# H05R1_Frontend_2.net
KiCad netlist of a schematic drawn in Altium Designer
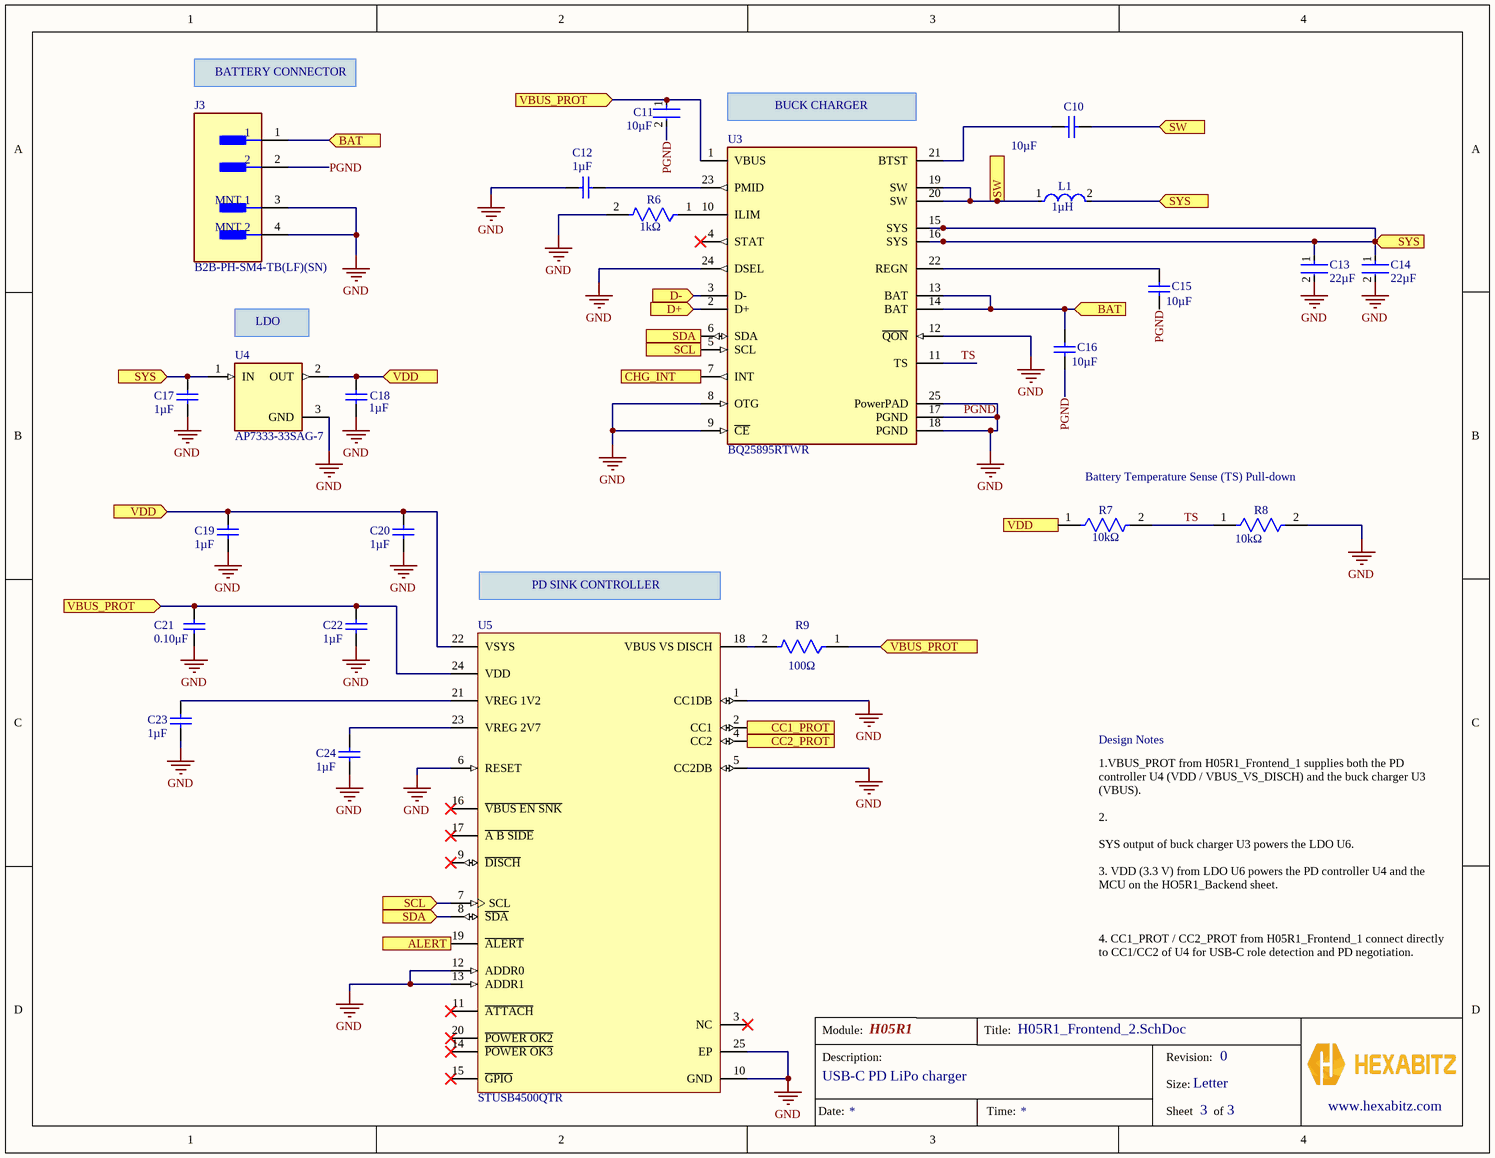
[diagram p0: H05R1_Frontend_2.SchDoc]

(export (version "E")
  (design (tool "Eeschema 10.0.6"))
  (components
    (comp (ref "C10")
      (value "10µF")
      (footprint "CAPC1608X90X35ML10T15")
      (fields
        (field (name "PART NUMBER") "GRM188R71C473KA01D")
        (field (name "MANUFACTURER") "Murata")
        (field (name "OCTOPART") "https://octopart.com/part/murata/GRM21BZ71E106KE15L")
      )
      (libsource (lib "Altium Content Vault") (part "CAP"))
    )
    (comp (ref "C11")
      (value "10µF")
      (footprint "FP-GRM21B-0_2-e0_2_0_7-IPC_B")
      (description "Chip Multilayer Ceramic Capacitors for General Purpose, 0805, 10uF, X7R, 15%, 10%, 25V")
      (fields (field (name "MPN") "GRM21BZ71E106KE15L"))
      (libsource (lib "Altium Content Vault") (part "b4654b650e69147ec39a6b967a45e02"))
    )
    (comp (ref "C12")
      (value "1µF")
      (footprint "CAPC1608X90X35ML10T15")
      (fields
        (field (name "MANUFACTURER") "Murata")
        (field (name "PART NUMBER") "GRM188R71C105KA12D")
        (field (name "OCTOPART") "https://octopart.com/search?q=GRM188R71C105KA12D&currency=USD&specs=0")
      )
      (libsource (lib "Altium Content Vault") (part "CAP"))
    )
    (comp (ref "C13")
      (value "22µF")
      (footprint "FP-GRM21B-0_15-MFG")
      (description "Chip Multilayer Ceramic Capacitors for General Purpose, 0805, 22uF, X5R, 15%, 20%, 6.3V")
      (fields (field (name "VOLTAGE") "6.3V") (field (name "TOLERANCE") "20%"))
      (libsource (lib "Altium Content Vault") (part "b4654b650e69147ec39a6b967a45e02"))
    )
    (comp (ref "C14")
      (value "22µF")
      (footprint "FP-GRM21B-0_15-MFG")
      (description "Chip Multilayer Ceramic Capacitors for General Purpose, 0805, 22uF, X5R, 15%, 20%, 6.3V")
      (fields (field (name "VOLTAGE") "6.3V") (field (name "TOLERANCE") "20%"))
      (libsource (lib "Altium Content Vault") (part "b4654b650e69147ec39a6b967a45e02"))
    )
    (comp (ref "C15")
      (value "10µF")
      (footprint "CAPC1608X90X35ML10T15")
      (fields
        (field (name "MANUFACTURER") "Murata")
        (field (name "PART NUMBER") "GRM188R71C105KA12D")
        (field (name "OCTOPART") "https://octopart.com/part/murata/GRM21BZ71E106KE15L")
      )
      (libsource (lib "Altium Content Vault") (part "CAP"))
    )
    (comp (ref "C16")
      (value "10µF")
      (footprint "CAPC2013X135X45ML10T25")
      (description "Multilayer Ceramic Capacitors MLCC Surface Mount 0805 10uF 6.3 Volts X5R")
      (fields (field (name "PART NUMBER") "GRM21BR60J106KE19L") (field (name "MANUFACTURER") "Murata"))
      (libsource (lib "Altium Content Vault") (part "CAP"))
    )
    (comp (ref "C17")
      (value "1µF")
      (footprint "CAPC1608X90X35ML10T15")
      (description "Ceramic Capacitor, Ceramic, 16V, 10% +Tol, 10% -Tol, X7R, 15% TC, 1uF, Surface Mount, 0603")
      (fields (field (name "MANUFACTURER") "Murata") (field (name "PART NUMBER") "GRM188R71C105KA12D"))
      (libsource (lib "Altium Content Vault") (part "CAP"))
    )
    (comp (ref "C18")
      (value "1µF")
      (footprint "CAPC1608X90X35ML10T15")
      (description "Ceramic Capacitor, Ceramic, 16V, 10% +Tol, 10% -Tol, X7R, 15% TC, 1uF, Surface Mount, 0603")
      (fields (field (name "MANUFACTURER") "Murata") (field (name "PART NUMBER") "GRM188R71C105KA12D"))
      (libsource (lib "Altium Content Vault") (part "CAP"))
    )
    (comp (ref "C19")
      (value "1µF")
      (footprint "MURA-0603_H_0.9_M")
      (description "CAP, Ceramic, 0.1 uF, 10%, 16 V, 0603, RoHS, Tape and Reel")
      (fields (field (name "MANUFACTURER") "Murata") (field (name "TOLERANCE") "10%"))
      (libsource (lib "Altium Content Vault") (part "CAP-NP-2"))
    )
    (comp (ref "C20")
      (value "1µF")
      (footprint "CAPC1608X90X35ML10T15")
      (description "Ceramic Capacitor, Ceramic, 16V, 10% +Tol, 10% -Tol, X7R, 15% TC, 1uF, Surface Mount, 0603")
      (fields (field (name "MANUFACTURER") "Murata") (field (name "PART NUMBER") "GRM188R71C105KA12D"))
      (libsource (lib "Altium Content Vault") (part "CAP"))
    )
    (comp (ref "C21")
      (value "0.10μF")
      (footprint "CAPC1608X90X35LL10T15")
      (description "25V 100Nf X7R 10% 0603 Multilayer Ceramic Capacitors Mlcc Smd/Smt Rohs")
      (fields (field (name "PART NUMBER") "GRM188R71E104KA01D") (field (name "MANUFACTURER") "Murata"))
      (libsource (lib "Altium Content Vault") (part "CAP"))
    )
    (comp (ref "C22")
      (value "1µF")
      (footprint "CAPC1608X90X35ML10T15")
      (fields
        (field (name "MANUFACTURER") "Murata")
        (field (name "PART NUMBER") "GRM188R71E105KA12D")
        (field (name "OCTOPART") "https://octopart.com/part/murata/GRM188R71E105KA12D")
      )
      (libsource (lib "Altium Content Vault") (part "CAP"))
    )
    (comp (ref "C23")
      (value "1µF")
      (footprint "CAPC1608X90X35ML10T15")
      (description "Ceramic Capacitor, Ceramic, 25V, 10% +Tol, 10% -Tol, X7R, 15% TC, 1uF, Surface Mount, 0603")
      (fields (field (name "MANUFACTURER") "Murata") (field (name "PART NUMBER") "GRM188R71E105KA12D"))
      (libsource (lib "Altium Content Vault") (part "CAP"))
    )
    (comp (ref "C24")
      (value "1µF")
      (footprint "CAPC1608X90X35ML10T15")
      (description "Ceramic Capacitor, Ceramic, 25V, 10% +Tol, 10% -Tol, X7R, 15% TC, 1uF, Surface Mount, 0603")
      (fields (field (name "MANUFACTURER") "Murata") (field (name "PART NUMBER") "GRM188R71E105KA12D"))
      (libsource (lib "Altium Content Vault") (part "CAP"))
    )
    (comp (ref "J3")
      (value "B2B-PH-SM4-TB(LF)(SN)")
      (footprint "FP-B2B-PH-SM4-TB_LF_SN-MFG")
      (description "CONN HEADER SMD 2POS 2MM")
      (fields (field (name "OCTOPART") "https://octopart.com/part/jst/B2B-PH-SM4-TB%28LF%29%28SN%29"))
      (libsource (lib "Altium Content Vault") (part "56ec3178a87b3978bdc1b3682cd516a"))
    )
    (comp (ref "L1")
      (value "1µH")
      (footprint "FP-XAL4020-102MEC-MFG")
      (description "Fixed Inductors 1uH 20% 9.6A 14.60mOhms AEC-Q200")
      (fields
        (field (name "MANUFACTURER") "Coilcraft")
        (field (name "OCTOPART") "https://octopart.com/xal4020-102mec-coilcraft-13142161")
      )
      (libsource (lib "Altium Content Vault") (part "725321dda6339637d4d059423bc1c3c"))
    )
    (comp (ref "R6")
      (value "1kΩ")
      (footprint "FP-RC0603-0_55-IPC_C")
      (description "RES 1K OHM 1% 1/10W 0603")
      (fields (field (name "TOLERANCE") "1%") (field (name "MPN") "RC0603FR-071KL"))
      (libsource (lib "Altium Content Vault") (part "1029c3af85768c4190bb7ad29bc67b5"))
    )
    (comp (ref "R7")
      (value "10kΩ")
      (footprint "FP-RC0603-0_55-IPC_C")
      (description "RES 10K OHM 1% 1/10W 0603")
      (fields
        (field (name "TOLERANCE") "1%")
        (field (name "OCTOPART") "https://octopart.com/search?q=RC0603FR-0710KL&currency=USD&specs=0")
      )
      (libsource (lib "Altium Content Vault") (part "1029c3af85768c4190bb7ad29bc67b5"))
    )
    (comp (ref "R8")
      (value "10kΩ")
      (footprint "FP-RC0603-0_55-IPC_C")
      (description "RES 10K OHM 1% 1/10W 0603")
      (fields
        (field (name "TOLERANCE") "1%")
        (field (name "OCTOPART") "https://octopart.com/search?q=RC0603FR-0710KL&currency=USD&specs=0")
      )
      (libsource (lib "Altium Content Vault") (part "1029c3af85768c4190bb7ad29bc67b5"))
    )
    (comp (ref "R9")
      (value "100Ω")
      (footprint "FP-RC0603-0_55-MFG")
      (fields (field (name "TOLERANCE") "1%") (field (name "MPN") "RC0603FR-07100RL"))
      (libsource (lib "Altium Content Vault") (part "1029c3af85768c4190bb7ad29bc67b5"))
    )
    (comp (ref "U3")
      (value "BQ25895RTWR")
      (footprint "FP-RTW0024H-IPC_B")
      (description "IC NVDC CHARGER I2C 24WQFN")
      (fields (field (name "OCTOPART") "https://octopart.com/bq25895rtwr-texas+instruments-56801238"))
      (libsource (lib "Altium Content Vault") (part "9676aa47796aa55c38f1d5ce4e9995c"))
    )
    (comp (ref "U4")
      (value "AP7333-33SAG-7")
      (footprint "FP-SOT23-MFG")
      (description "IC REG LINEAR 3.3V 300MA SOT23-3")
      (fields
        (field (name "MANUFACTURER") "Diodes Inc.")
        (field (name "OCTOPART") "https://octopart.com/ap7333-33sag-7-diodes+inc.-17947531")
      )
      (libsource (lib "Altium Content Vault") (part "99e442a359f93c082ad1a9b51a2d33f"))
    )
    (comp (ref "U5")
      (value "STUSB4500QTR")
      (footprint "FP-QFN-24-EP_4x4-MFG")
      (description "4.1V~22V USB 2.0 I2C Controllers Interface ICs STUSB45 Controller 24-VFQFN Exposed Pad")
      (fields (field (name "OCTOPART") "https://octopart.com/stusb4500qtr-stmicroelectronics-91765108"))
      (libsource (lib "Altium Content Vault") (part "STUSB4500QTR"))
    )
  )
  (nets
    (net (code "1") (name "/ALERT") (class "Default")
      (node (ref "U5") (pin "19") (pinfunction "~{ALERT}_19") (pintype "open_collector"))
    )
    (net (code "2") (name "/BAT") (class "Default")
      (node (ref "C16") (pin "2") (pinfunction "2_2") (pintype "passive"))
      (node (ref "J3") (pin "1") (pinfunction "1_1") (pintype "passive"))
      (node (ref "U3") (pin "13") (pinfunction "BAT_13") (pintype "power_in"))
      (node (ref "U3") (pin "14") (pinfunction "BAT_14") (pintype "power_in"))
    )
    (net (code "3") (name "/CC1_PROT") (class "Default")
      (node (ref "U5") (pin "2") (pinfunction "CC1_2") (pintype "bidirectional"))
    )
    (net (code "4") (name "/CC2_PROT") (class "Default")
      (node (ref "U5") (pin "4") (pinfunction "CC2_4") (pintype "bidirectional"))
    )
    (net (code "5") (name "/CHG_INT") (class "Default")
      (node (ref "U3") (pin "7") (pinfunction "INT_7") (pintype "output"))
    )
    (net (code "6") (name "/D+") (class "Default")
      (node (ref "U3") (pin "2") (pinfunction "D+_2") (pintype "passive"))
    )
    (net (code "7") (name "/D-") (class "Default")
      (node (ref "U3") (pin "3") (pinfunction "D-_3") (pintype "passive"))
    )
    (net (code "8") (name "/SCL") (class "Default")
      (node (ref "U3") (pin "5") (pinfunction "SCL_5") (pintype "input"))
      (node (ref "U5") (pin "7") (pinfunction "SCL_7") (pintype "input"))
    )
    (net (code "9") (name "/SDA") (class "Default")
      (node (ref "U3") (pin "6") (pinfunction "SDA_6") (pintype "bidirectional"))
      (node (ref "U5") (pin "8") (pinfunction "~{SDA}_8") (pintype "bidirectional"))
    )
    (net (code "10") (name "/SW") (class "Default")
      (node (ref "C10") (pin "1") (pinfunction "1_1") (pintype "passive"))
      (node (ref "L1") (pin "1") (pinfunction "1_1") (pintype "passive"))
      (node (ref "U3") (pin "19") (pinfunction "SW_19") (pintype "passive"))
      (node (ref "U3") (pin "20") (pinfunction "SW_20") (pintype "passive"))
    )
    (net (code "11") (name "/SYS") (class "Default")
      (node (ref "C13") (pin "1") (pinfunction "1_1") (pintype "passive"))
      (node (ref "C14") (pin "1") (pinfunction "1_1") (pintype "passive"))
      (node (ref "C17") (pin "2") (pinfunction "2_2") (pintype "passive"))
      (node (ref "L1") (pin "2") (pinfunction "2_2") (pintype "passive"))
      (node (ref "U3") (pin "15") (pinfunction "SYS_15") (pintype "power_in"))
      (node (ref "U3") (pin "16") (pinfunction "SYS_16") (pintype "power_in"))
      (node (ref "U4") (pin "1") (pinfunction "IN_1") (pintype "input"))
    )
    (net (code "12") (name "/TS") (class "Default")
      (node (ref "R7") (pin "2") (pinfunction "2_2") (pintype "passive"))
      (node (ref "R8") (pin "1") (pinfunction "1_1") (pintype "passive"))
      (node (ref "U3") (pin "11") (pinfunction "TS_11") (pintype "passive"))
    )
    (net (code "13") (name "/VBUS_PROT") (class "Default")
      (node (ref "C11") (pin "1") (pinfunction "1_1") (pintype "passive"))
      (node (ref "C21") (pin "2") (pinfunction "2_2") (pintype "passive"))
      (node (ref "C22") (pin "2") (pinfunction "2_2") (pintype "passive"))
      (node (ref "R9") (pin "1") (pinfunction "1_1") (pintype "passive"))
      (node (ref "U3") (pin "1") (pinfunction "VBUS_1") (pintype "power_in"))
      (node (ref "U5") (pin "24") (pinfunction "VDD_24") (pintype "power_in"))
    )
    (net (code "14") (name "/VDD") (class "Default")
      (node (ref "C18") (pin "2") (pinfunction "2_2") (pintype "passive"))
      (node (ref "C19") (pin "2") (pinfunction "2_2") (pintype "passive"))
      (node (ref "C20") (pin "2") (pinfunction "2_2") (pintype "passive"))
      (node (ref "R7") (pin "1") (pinfunction "1_1") (pintype "passive"))
      (node (ref "U4") (pin "2") (pinfunction "OUT_2") (pintype "output"))
      (node (ref "U5") (pin "22") (pinfunction "VSYS_22") (pintype "power_in"))
    )
    (net (code "15") (name "GND") (class "Default")
      (node (ref "C11") (pin "2") (pinfunction "2_2") (pintype "passive"))
      (node (ref "C12") (pin "1") (pinfunction "1_1") (pintype "passive"))
      (node (ref "C13") (pin "2") (pinfunction "2_2") (pintype "passive"))
      (node (ref "C14") (pin "2") (pinfunction "2_2") (pintype "passive"))
      (node (ref "C15") (pin "1") (pinfunction "1_1") (pintype "passive"))
      (node (ref "C16") (pin "1") (pinfunction "1_1") (pintype "passive"))
      (node (ref "C17") (pin "1") (pinfunction "1_1") (pintype "passive"))
      (node (ref "C18") (pin "1") (pinfunction "1_1") (pintype "passive"))
      (node (ref "C19") (pin "1") (pinfunction "1_1") (pintype "passive"))
      (node (ref "C20") (pin "1") (pinfunction "1_1") (pintype "passive"))
      (node (ref "C21") (pin "1") (pinfunction "1_1") (pintype "passive"))
      (node (ref "C22") (pin "1") (pinfunction "1_1") (pintype "passive"))
      (node (ref "C23") (pin "1") (pinfunction "1_1") (pintype "passive"))
      (node (ref "C24") (pin "1") (pinfunction "1_1") (pintype "passive"))
      (node (ref "J3") (pin "2") (pinfunction "2_2") (pintype "passive"))
      (node (ref "J3") (pin "3") (pinfunction "MNT_1_3") (pintype "passive"))
      (node (ref "J3") (pin "4") (pinfunction "MNT_2_4") (pintype "passive"))
      (node (ref "R6") (pin "2") (pinfunction "2_2") (pintype "passive"))
      (node (ref "R8") (pin "2") (pinfunction "2_2") (pintype "passive"))
      (node (ref "U3") (pin "12") (pinfunction "~{QON}_12") (pintype "input"))
      (node (ref "U3") (pin "17") (pinfunction "PGND_17") (pintype "power_in"))
      (node (ref "U3") (pin "18") (pinfunction "PGND_18") (pintype "power_in"))
      (node (ref "U3") (pin "24") (pinfunction "DSEL_24") (pintype "output"))
      (node (ref "U3") (pin "25") (pinfunction "PowerPAD_25") (pintype "power_in"))
      (node (ref "U3") (pin "8") (pinfunction "OTG_8") (pintype "input"))
      (node (ref "U3") (pin "9") (pinfunction "~{CE}_9") (pintype "input"))
      (node (ref "U4") (pin "3") (pinfunction "GND_3") (pintype "power_in"))
      (node (ref "U5") (pin "1") (pinfunction "CC1DB_1") (pintype "bidirectional"))
      (node (ref "U5") (pin "10") (pinfunction "GND_10") (pintype "power_in"))
      (node (ref "U5") (pin "12") (pinfunction "ADDR0_12") (pintype "input"))
      (node (ref "U5") (pin "13") (pinfunction "ADDR1_13") (pintype "input"))
      (node (ref "U5") (pin "25") (pinfunction "EP_25") (pintype "power_in"))
      (node (ref "U5") (pin "5") (pinfunction "CC2DB_5") (pintype "bidirectional"))
      (node (ref "U5") (pin "6") (pinfunction "RESET_6") (pintype "input"))
    )
    (net (code "16") (name "Net-(U3-BTST)") (class "Default")
      (node (ref "C10") (pin "2") (pinfunction "2_2") (pintype "passive"))
      (node (ref "U3") (pin "21") (pinfunction "BTST_21") (pintype "power_in"))
    )
    (net (code "17") (name "Net-(U3-ILIM)") (class "Default")
      (node (ref "R6") (pin "1") (pinfunction "1_1") (pintype "passive"))
      (node (ref "U3") (pin "10") (pinfunction "ILIM_10") (pintype "passive"))
    )
    (net (code "18") (name "Net-(U3-PMID)") (class "Default")
      (node (ref "C12") (pin "2") (pinfunction "2_2") (pintype "passive"))
      (node (ref "U3") (pin "23") (pinfunction "PMID_23") (pintype "output"))
    )
    (net (code "19") (name "Net-(U3-REGN)") (class "Default")
      (node (ref "C15") (pin "2") (pinfunction "2_2") (pintype "passive"))
      (node (ref "U3") (pin "22") (pinfunction "REGN_22") (pintype "power_in"))
    )
    (net (code "20") (name "Net-(U5-VBUS_VS_DISCH)") (class "Default")
      (node (ref "R9") (pin "2") (pinfunction "2_2") (pintype "passive"))
      (node (ref "U5") (pin "18") (pinfunction "VBUS_VS_DISCH_18") (pintype "power_in"))
    )
    (net (code "21") (name "Net-(U5-VREG_1V2)") (class "Default")
      (node (ref "C23") (pin "2") (pinfunction "2_2") (pintype "passive"))
      (node (ref "U5") (pin "21") (pinfunction "VREG_1V2_21") (pintype "power_in"))
    )
    (net (code "22") (name "Net-(U5-VREG_2V7)") (class "Default")
      (node (ref "C24") (pin "2") (pinfunction "2_2") (pintype "passive"))
      (node (ref "U5") (pin "23") (pinfunction "VREG_2V7_23") (pintype "power_in"))
    )
    (net (code "23") (name "unconnected-(U3-STAT-Pad4)") (class "Default")
      (node (ref "U3") (pin "4") (pinfunction "STAT_4") (pintype "output+no_connect"))
    )
    (net (code "24") (name "unconnected-(U5-NC-Pad3)") (class "Default")
      (node (ref "U5") (pin "3") (pinfunction "NC_3") (pintype "passive+no_connect"))
    )
    (net (code "25") (name "unconnected-(U5-~{ATTACH}-Pad11)") (class "Default")
      (node (ref "U5") (pin "11") (pinfunction "~{ATTACH}_11") (pintype "open_collector+no_connect"))
    )
    (net (code "26") (name "unconnected-(U5-~{A_B_SIDE}-Pad17)") (class "Default")
      (node (ref "U5") (pin "17") (pinfunction "~{A_B_SIDE}_17") (pintype "open_collector+no_connect"))
    )
    (net (code "27") (name "unconnected-(U5-~{DISCH}-Pad9)") (class "Default")
      (node (ref "U5") (pin "9") (pinfunction "~{DISCH}_9") (pintype "bidirectional+no_connect"))
    )
    (net (code "28") (name "unconnected-(U5-~{GPIO}-Pad15)") (class "Default")
      (node (ref "U5") (pin "15") (pinfunction "~{GPIO}_15") (pintype "open_collector+no_connect"))
    )
    (net (code "29") (name "unconnected-(U5-~{POWER_OK2}-Pad20)") (class "Default")
      (node (ref "U5") (pin "20") (pinfunction "~{POWER_OK2}_20") (pintype "power_in+no_connect"))
    )
    (net (code "30") (name "unconnected-(U5-~{POWER_OK3}-Pad14)") (class "Default")
      (node (ref "U5") (pin "14") (pinfunction "~{POWER_OK3}_14") (pintype "open_collector+no_connect"))
    )
    (net (code "31") (name "unconnected-(U5-~{VBUS_EN_SNK}-Pad16)") (class "Default")
      (node (ref "U5") (pin "16") (pinfunction "~{VBUS_EN_SNK}_16") (pintype "open_collector+no_connect"))
    )
  )
)
